# buck.net
KiCad netlist of a schematic drawn in Altium Designer
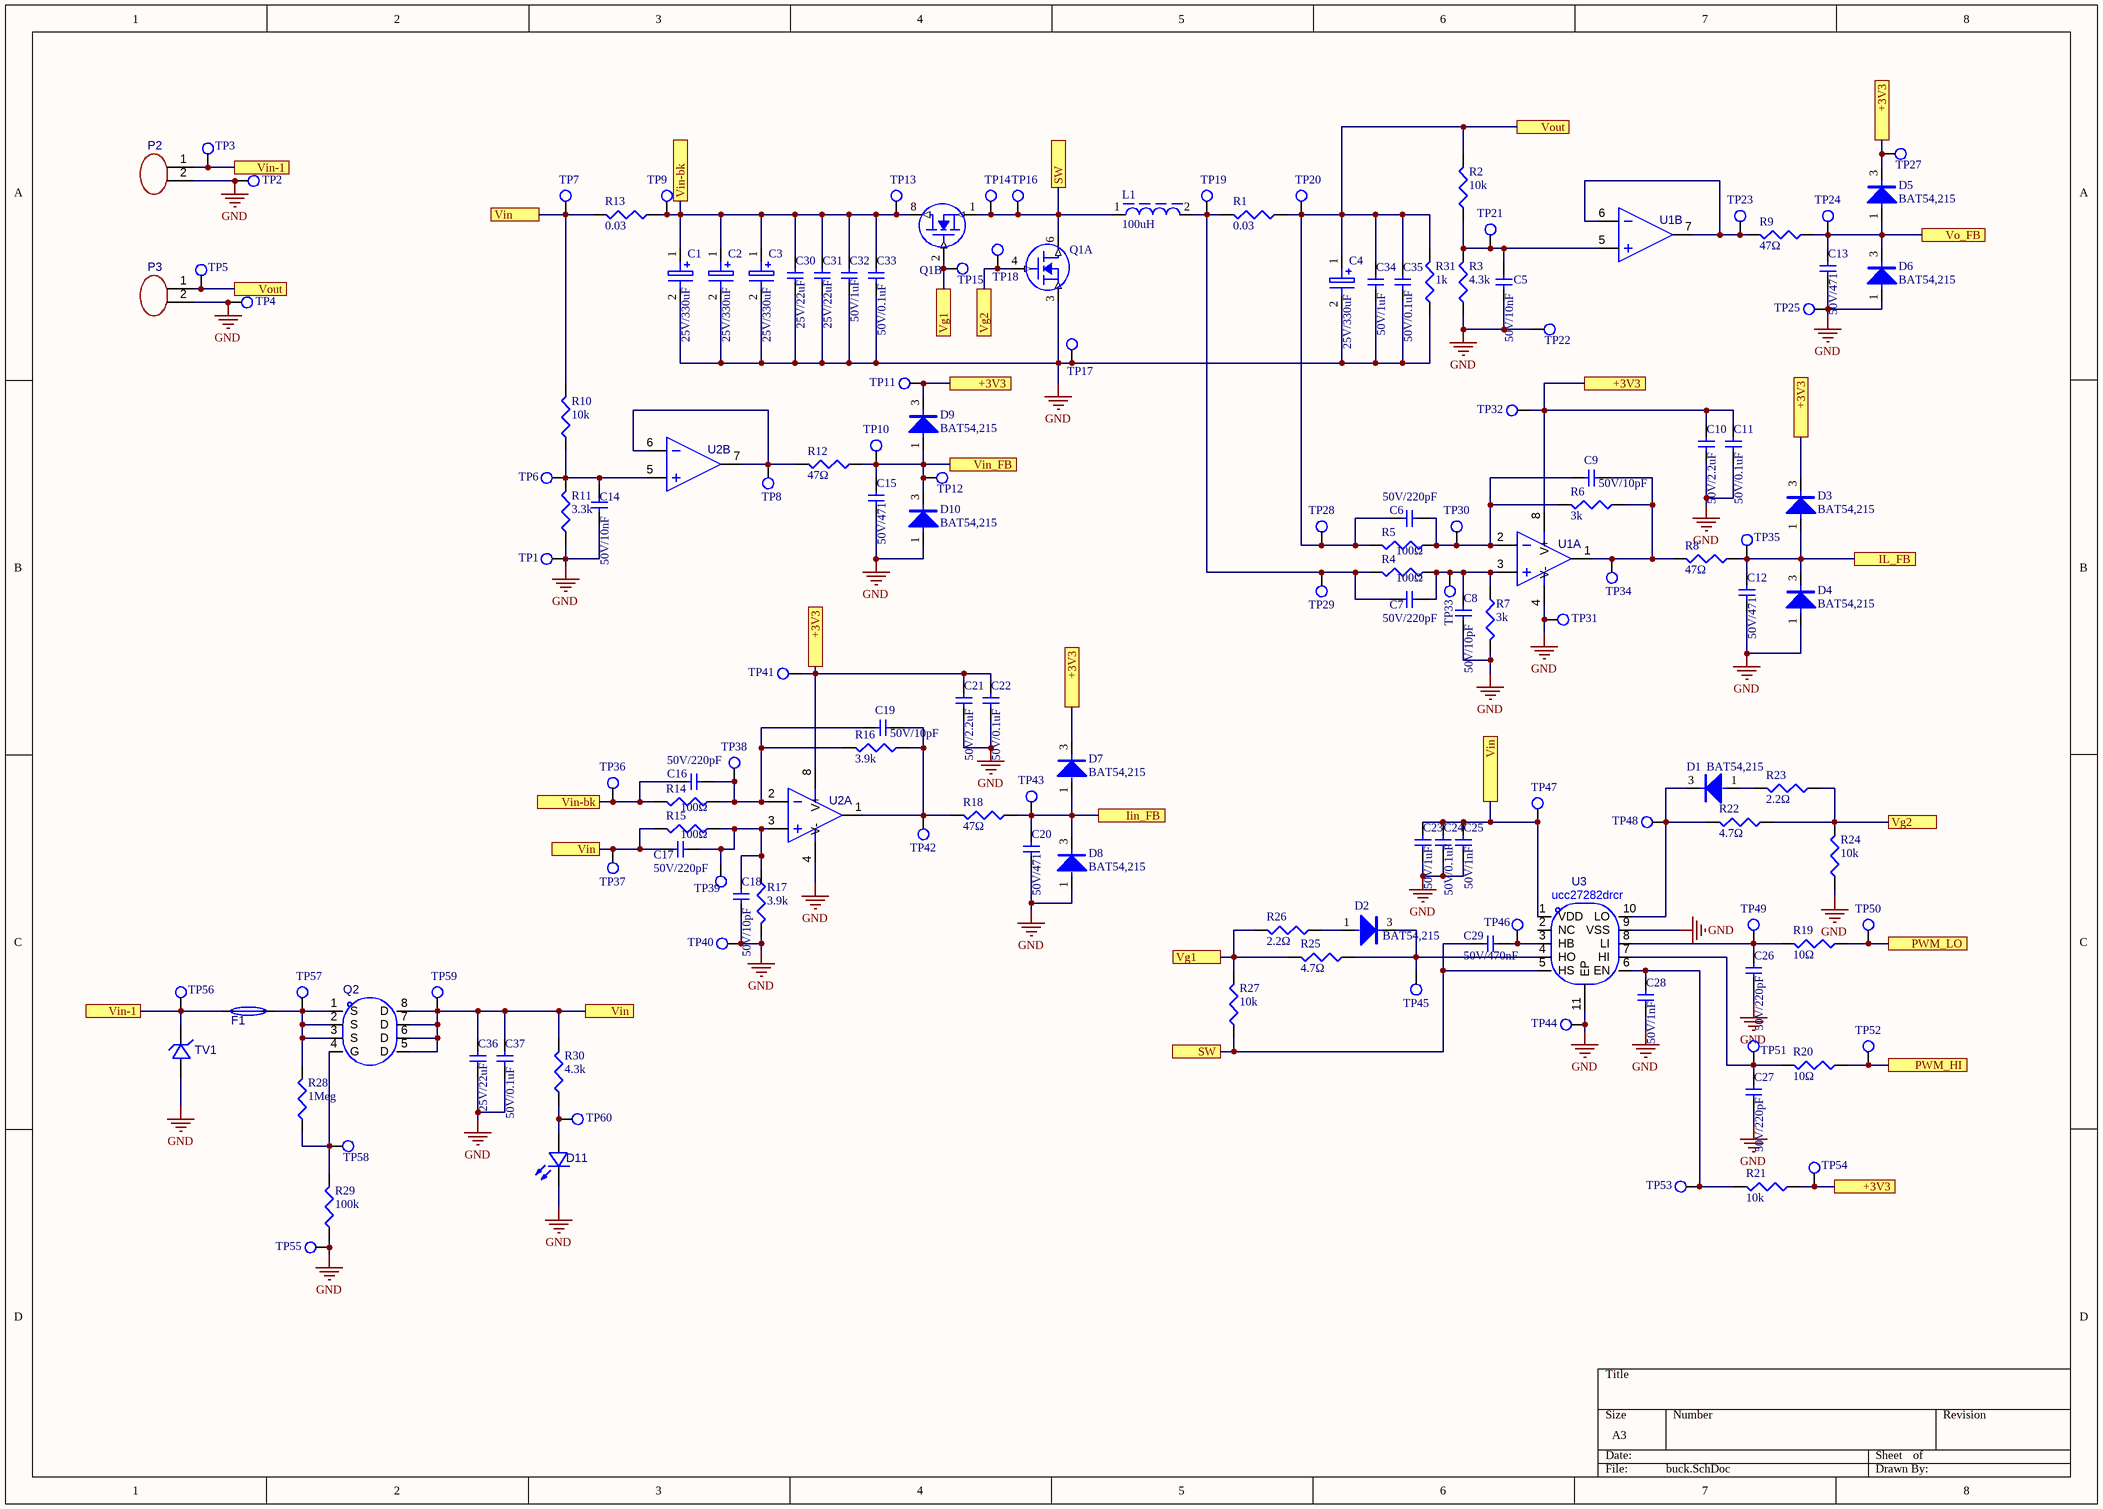
[diagram p0: buck.SchDoc]

(export (version "E")
  (design (tool "Eeschema 10.0.6"))
  (components
    (comp (ref "C1")
      (value "25V/330uF")
      (footprint "CAP-TH_BD8.0-P3.50-D0.6-FD")
      (description "25V/330uF,ERS1EM331F12OT,艾华,插件,D8xL12mm,irms=850mA,esr=0.086,")
      (libsource (lib "60W-PD-V2") (part "电解电容25V/330uF"))
    )
    (comp (ref "C2")
      (value "25V/330uF")
      (footprint "CAP-TH_BD8.0-P3.50-D0.6-FD")
      (description "25V/330uF,ERS1EM331F12OT,艾华,插件,D8xL12mm,irms=850mA,esr=0.086,")
      (libsource (lib "60W-PD-V2") (part "电解电容25V/330uF"))
    )
    (comp (ref "C3")
      (value "25V/330uF")
      (footprint "CAP-TH_BD8.0-P3.50-D0.6-FD")
      (description "25V/330uF,ERS1EM331F12OT,艾华,插件,D8xL12mm,irms=850mA,esr=0.086,")
      (libsource (lib "60W-PD-V2") (part "电解电容25V/330uF"))
    )
    (comp (ref "C4")
      (value "25V/330uF")
      (footprint "CAP-TH_BD8.0-P3.50-D0.6-FD")
      (description "25V/330uF,ERS1EM331F12OT,艾华,插件,D8xL12mm,irms=850mA,esr=0.086,")
      (libsource (lib "60W-PD-V2") (part "电解电容25V/330uF"))
    )
    (comp (ref "C5")
      (value "50V/10nF")
      (footprint "C0603")
      (description "0603,50V/10nF")
      (libsource (lib "60W-PD-V2") (part "C0603-50V/10nF"))
    )
    (comp (ref "C6")
      (value "50V/220pF")
      (footprint "C0603")
      (description "0603,50V/220pF")
      (libsource (lib "60W-PD-V2") (part "C0603-50V/220pF"))
    )
    (comp (ref "C7")
      (value "50V/220pF")
      (footprint "C0603")
      (description "0603,50V/220pF")
      (libsource (lib "60W-PD-V2") (part "C0603-50V/220pF"))
    )
    (comp (ref "C8")
      (value "50V/10pF")
      (footprint "C0603")
      (description "0603,50V/10pF")
      (libsource (lib "60W-PD-V2") (part "C0603-50V/10pF"))
    )
    (comp (ref "C9")
      (value "50V/10pF")
      (footprint "C0603")
      (description "0603,50V/10pF")
      (libsource (lib "60W-PD-V2") (part "C0603-50V/10pF"))
    )
    (comp (ref "C10")
      (value "50V/2.2uF")
      (footprint "C0805")
      (description "0805,50V/2.2uF,")
      (libsource (lib "60W-PD-V2") (part "C0805-50V/2.2uF"))
    )
    (comp (ref "C11")
      (value "50V/0.1uF")
      (footprint "C0603")
      (description "0603,50V/104")
      (libsource (lib "60W-PD-V2") (part "C0603-50V/104"))
    )
    (comp (ref "C12")
      (value "50V/471")
      (footprint "C0603")
      (description "0603,50V/471,")
      (libsource (lib "60W-PD-V2") (part "C0603-50V/471"))
    )
    (comp (ref "C13")
      (value "50V/471")
      (footprint "C0603")
      (description "0603,50V/471,")
      (libsource (lib "60W-PD-V2") (part "C0603-50V/471"))
    )
    (comp (ref "C14")
      (value "50V/10nF")
      (footprint "C0603")
      (description "0603,50V/10nF")
      (libsource (lib "60W-PD-V2") (part "C0603-50V/10nF"))
    )
    (comp (ref "C15")
      (value "50V/471")
      (footprint "C0603")
      (description "0603,50V/471,")
      (libsource (lib "60W-PD-V2") (part "C0603-50V/471"))
    )
    (comp (ref "C16")
      (value "50V/220pF")
      (footprint "C0603")
      (description "0603,50V/220pF")
      (libsource (lib "60W-PD-V2") (part "C0603-50V/220pF"))
    )
    (comp (ref "C17")
      (value "50V/220pF")
      (footprint "C0603")
      (description "0603,50V/220pF")
      (libsource (lib "60W-PD-V2") (part "C0603-50V/220pF"))
    )
    (comp (ref "C18")
      (value "50V/10pF")
      (footprint "C0603")
      (description "0603,50V/10pF")
      (libsource (lib "60W-PD-V2") (part "C0603-50V/10pF"))
    )
    (comp (ref "C19")
      (value "50V/10pF")
      (footprint "C0603")
      (description "0603,50V/10pF")
      (libsource (lib "60W-PD-V2") (part "C0603-50V/10pF"))
    )
    (comp (ref "C20")
      (value "50V/471")
      (footprint "C0603")
      (description "0603,50V/471,")
      (libsource (lib "60W-PD-V2") (part "C0603-50V/471"))
    )
    (comp (ref "C21")
      (value "50V/2.2uF")
      (footprint "C0805")
      (description "0805,50V/2.2uF,")
      (libsource (lib "60W-PD-V2") (part "C0805-50V/2.2uF"))
    )
    (comp (ref "C22")
      (value "50V/0.1uF")
      (footprint "C0603")
      (description "0603,50V/104")
      (libsource (lib "60W-PD-V2") (part "C0603-50V/104"))
    )
    (comp (ref "C23")
      (value "50V/1uF")
      (footprint "C0603")
      (description "0603,50V/1uF")
      (libsource (lib "60W-PD-V2") (part "C0603-50V/1uF"))
    )
    (comp (ref "C24")
      (value "50V/0.1uF")
      (footprint "C0603")
      (description "0603,50V/104")
      (libsource (lib "60W-PD-V2") (part "C0603-50V/104"))
    )
    (comp (ref "C25")
      (value "50V/1nF")
      (footprint "C0603")
      (description "0603,50V/1nF")
      (libsource (lib "60W-PD-V2") (part "C0603-50V/1nF"))
    )
    (comp (ref "C26")
      (value "50V/220pF")
      (footprint "C0603")
      (description "0603,50V/220pF")
      (libsource (lib "60W-PD-V2") (part "C0603-50V/220pF"))
    )
    (comp (ref "C27")
      (value "50V/220pF")
      (footprint "C0603")
      (description "0603,50V/220pF")
      (libsource (lib "60W-PD-V2") (part "C0603-50V/220pF"))
    )
    (comp (ref "C28")
      (value "50V/1nF")
      (footprint "C0603")
      (description "0603,50V/1nF")
      (libsource (lib "60W-PD-V2") (part "C0603-50V/1nF"))
    )
    (comp (ref "C29")
      (value "50V/470nF")
      (footprint "C0603")
      (description "0603,50V/470nF")
      (libsource (lib "60W-PD-V2") (part "C0603-50V/470nF"))
    )
    (comp (ref "C30")
      (value "25V/22uF")
      (footprint "C0805")
      (description "0805,25V/22uF,")
      (libsource (lib "60W-PD-V2") (part "C0805-25V/22uF"))
    )
    (comp (ref "C31")
      (value "25V/22uF")
      (footprint "C0805")
      (description "0805,25V/22uF,")
      (libsource (lib "60W-PD-V2") (part "C0805-25V/22uF"))
    )
    (comp (ref "C32")
      (value "50V/1uF")
      (footprint "C0603")
      (description "0603,50V/1uF")
      (libsource (lib "60W-PD-V2") (part "C0603-50V/1uF"))
    )
    (comp (ref "C33")
      (value "50V/0.1uF")
      (footprint "C0603")
      (description "0603,50V/104")
      (libsource (lib "60W-PD-V2") (part "C0603-50V/104"))
    )
    (comp (ref "C34")
      (value "50V/1uF")
      (footprint "C0603")
      (description "0603,50V/1uF")
      (libsource (lib "60W-PD-V2") (part "C0603-50V/1uF"))
    )
    (comp (ref "C35")
      (value "50V/0.1uF")
      (footprint "C0603")
      (description "0603,50V/104")
      (libsource (lib "60W-PD-V2") (part "C0603-50V/104"))
    )
    (comp (ref "C36")
      (value "25V/22uF")
      (footprint "C0805")
      (description "0805,25V/22uF,")
      (libsource (lib "60W-PD-V2") (part "C0805-25V/22uF"))
    )
    (comp (ref "C37")
      (value "50V/0.1uF")
      (footprint "C0603")
      (description "0603,50V/104")
      (libsource (lib "60W-PD-V2") (part "C0603-50V/104"))
    )
    (comp (ref "D1")
      (value "BAT54,215")
      (footprint "SOT-23_L2.9-W1.3-P1.90-LS2.4-BR")
      (description "BAT54,215,安世,SOT-23,肖特基二极管")
      (libsource (lib "60W-PD-V2") (part "二极管-BAT54,215"))
    )
    (comp (ref "D2")
      (value "BAT54,215")
      (footprint "SOT-23_L2.9-W1.3-P1.90-LS2.4-BR")
      (description "BAT54,215,安世,SOT-23,肖特基二极管")
      (libsource (lib "60W-PD-V2") (part "二极管-BAT54,215"))
    )
    (comp (ref "D3")
      (value "BAT54,215")
      (footprint "SOT-23_L2.9-W1.3-P1.90-LS2.4-BR")
      (description "BAT54,215,安世,SOT-23,肖特基二极管")
      (libsource (lib "60W-PD-V2") (part "二极管-BAT54,215"))
    )
    (comp (ref "D4")
      (value "BAT54,215")
      (footprint "SOT-23_L2.9-W1.3-P1.90-LS2.4-BR")
      (description "BAT54,215,安世,SOT-23,肖特基二极管")
      (libsource (lib "60W-PD-V2") (part "二极管-BAT54,215"))
    )
    (comp (ref "D5")
      (value "BAT54,215")
      (footprint "SOT-23_L2.9-W1.3-P1.90-LS2.4-BR")
      (description "BAT54,215,安世,SOT-23,肖特基二极管")
      (libsource (lib "60W-PD-V2") (part "二极管-BAT54,215"))
    )
    (comp (ref "D6")
      (value "BAT54,215")
      (footprint "SOT-23_L2.9-W1.3-P1.90-LS2.4-BR")
      (description "BAT54,215,安世,SOT-23,肖特基二极管")
      (libsource (lib "60W-PD-V2") (part "二极管-BAT54,215"))
    )
    (comp (ref "D7")
      (value "BAT54,215")
      (footprint "SOT-23_L2.9-W1.3-P1.90-LS2.4-BR")
      (description "BAT54,215,安世,SOT-23,肖特基二极管")
      (libsource (lib "60W-PD-V2") (part "二极管-BAT54,215"))
    )
    (comp (ref "D8")
      (value "BAT54,215")
      (footprint "SOT-23_L2.9-W1.3-P1.90-LS2.4-BR")
      (description "BAT54,215,安世,SOT-23,肖特基二极管")
      (libsource (lib "60W-PD-V2") (part "二极管-BAT54,215"))
    )
    (comp (ref "D9")
      (value "BAT54,215")
      (footprint "SOT-23_L2.9-W1.3-P1.90-LS2.4-BR")
      (description "BAT54,215,安世,SOT-23,肖特基二极管")
      (libsource (lib "60W-PD-V2") (part "二极管-BAT54,215"))
    )
    (comp (ref "D10")
      (value "BAT54,215")
      (footprint "SOT-23_L2.9-W1.3-P1.90-LS2.4-BR")
      (description "BAT54,215,安世,SOT-23,肖特基二极管")
      (libsource (lib "60W-PD-V2") (part "二极管-BAT54,215"))
    )
    (comp (ref "D11")
      (value "ncd0805c1")
      (footprint "LED0805-RD")
      (fields (field (name "MANUFACTURER") "国星光电") (field (name "MANUFACTURERPART") "NCD0805C1"))
      (libsource (lib "60W-PD-V2") (part "ncd0805c1"))
    )
    (comp (ref "F1")
      (value "bsmd1206c-1400t")
      (footprint "F1206")
      (description "类型:贴片式保险丝;额定电流:4A;额定电压 (AC):72V;额定电压:72V;分断能力:50A;")
      (fields (field (name "MANUFACTURER") "BHFUSE(佰宏)") (field (name "MANUFACTURERPART") "BSMD1206C-1400T"))
      (libsource (lib "60W-PD-V2") (part "bsmd1206c-1400t"))
    )
    (comp (ref "L1")
      (value "100uH")
      (footprint "IND-SMD_L13.5-W12.6")
      (description "100uH/5.5A,SMD,XR1365-101M,SMD,13.5x12.6mm,XR(祥如),i=5.5A,isat=7.5A")
      (libsource (lib "60W-PD-V2") (part "电感-100uH/5A"))
    )
    (comp (ref "P2")
      (value "wj500v-5.08-2p")
      (footprint "CONN-TH_2P-P5.00_WJ500V-5.08-2P")
      (fields
        (field (name "MANUFACTURER") "KANGNEX(康奈克斯电气)")
        (field (name "MANUFACTURERPART") "WJ500V-5.08-2P")
      )
      (libsource (lib "60W-PD-V2") (part "wj500v-5.08-2p"))
    )
    (comp (ref "P3")
      (value "wj500v-5.08-2p")
      (footprint "CONN-TH_2P-P5.00_WJ500V-5.08-2P")
      (fields
        (field (name "MANUFACTURER") "KANGNEX(康奈克斯电气)")
        (field (name "MANUFACTURERPART") "WJ500V-5.08-2P")
      )
      (libsource (lib "60W-PD-V2") (part "wj500v-5.08-2p"))
    )
    (comp (ref "Q1")
      (value "NCE6005AS")
      (footprint "SOP-8_L4.9-W3.9-P1.27-LS6.0-BL-2mos")
      (description "NCE6005AS,60V/5A,Rdson=35m,新洁能,2个N沟道")
      (libsource (lib "60W-PD-V2") (part "MOS管-60V/5A"))
    )
    (comp (ref "Q2")
      (value "ao4407a_c2841482")
      (footprint "SOP-8_L5.0-W4.0-P1.27-LS6.0-BL")
      (fields (field (name "MANUFACTURER") "UMW(友台半导体)") (field (name "MANUFACTURERPART") "AO4407A"))
      (libsource (lib "60W-PD-V2") (part "ao4407a_c2841482"))
    )
    (comp (ref "R1")
      (value "0.03")
      (footprint "R0805")
      (description "0805,0.03,RE0805FAR030,捷而瑞")
      (libsource (lib "60W-PD-V2") (part "R0805-0R03"))
    )
    (comp (ref "R2")
      (value "10k")
      (footprint "R0603")
      (description "0603,10k")
      (libsource (lib "60W-PD-V2") (part "R0603-10k"))
    )
    (comp (ref "R3")
      (value "4.3k")
      (footprint "R0603")
      (description "0603,4.3k")
      (libsource (lib "60W-PD-V2") (part "R0603-4.3k"))
    )
    (comp (ref "R4")
      (value "100Ω")
      (footprint "R0603")
      (description "0603,100Ω")
      (libsource (lib "60W-PD-V2") (part "R0603-100Ω"))
    )
    (comp (ref "R5")
      (value "100Ω")
      (footprint "R0603")
      (description "0603,100Ω")
      (libsource (lib "60W-PD-V2") (part "R0603-100Ω"))
    )
    (comp (ref "R6")
      (value "3k")
      (footprint "R0603")
      (description "0603,3k")
      (libsource (lib "60W-PD-V2") (part "R0603-3k"))
    )
    (comp (ref "R7")
      (value "3k")
      (footprint "R0603")
      (description "0603,3k")
      (libsource (lib "60W-PD-V2") (part "R0603-3k"))
    )
    (comp (ref "R8")
      (value "47Ω")
      (footprint "R0603")
      (description "0603,47Ω")
      (libsource (lib "60W-PD-V2") (part "R0603-47Ω"))
    )
    (comp (ref "R9")
      (value "47Ω")
      (footprint "R0603")
      (description "0603,47Ω")
      (libsource (lib "60W-PD-V2") (part "R0603-47Ω"))
    )
    (comp (ref "R10")
      (value "10k")
      (footprint "R0603")
      (description "0603,10k")
      (libsource (lib "60W-PD-V2") (part "R0603-10k"))
    )
    (comp (ref "R11")
      (value "3.3k")
      (footprint "R0603")
      (description "0603,3.3k")
      (libsource (lib "60W-PD-V2") (part "R0603-3.3k"))
    )
    (comp (ref "R12")
      (value "47Ω")
      (footprint "R0603")
      (description "0603,47Ω")
      (libsource (lib "60W-PD-V2") (part "R0603-47Ω"))
    )
    (comp (ref "R13")
      (value "0.03")
      (footprint "R0805")
      (description "0805,0.03,RE0805FAR030,捷而瑞")
      (libsource (lib "60W-PD-V2") (part "R0805-0R03"))
    )
    (comp (ref "R14")
      (value "100Ω")
      (footprint "R0603")
      (description "0603,100Ω")
      (libsource (lib "60W-PD-V2") (part "R0603-100Ω"))
    )
    (comp (ref "R15")
      (value "100Ω")
      (footprint "R0603")
      (description "0603,100Ω")
      (libsource (lib "60W-PD-V2") (part "R0603-100Ω"))
    )
    (comp (ref "R16")
      (value "3.9k")
      (footprint "R0603")
      (description "0603,3.9k")
      (libsource (lib "60W-PD-V2") (part "R0603-3.9k"))
    )
    (comp (ref "R17")
      (value "3.9k")
      (footprint "R0603")
      (description "0603,3.9k")
      (libsource (lib "60W-PD-V2") (part "R0603-3.9k"))
    )
    (comp (ref "R18")
      (value "47Ω")
      (footprint "R0603")
      (description "0603,47Ω")
      (libsource (lib "60W-PD-V2") (part "R0603-47Ω"))
    )
    (comp (ref "R19")
      (value "10Ω")
      (footprint "R0603")
      (description "0603,10Ω")
      (libsource (lib "60W-PD-V2") (part "R0603-10Ω"))
    )
    (comp (ref "R20")
      (value "10Ω")
      (footprint "R0603")
      (description "0603,10Ω")
      (libsource (lib "60W-PD-V2") (part "R0603-10Ω"))
    )
    (comp (ref "R21")
      (value "10k")
      (footprint "R0603")
      (description "0603,10k")
      (libsource (lib "60W-PD-V2") (part "R0603-10k"))
    )
    (comp (ref "R22")
      (value "4.7Ω")
      (footprint "R0603")
      (description "0603,4.7Ω")
      (libsource (lib "60W-PD-V2") (part "R0603-4.7Ω"))
    )
    (comp (ref "R23")
      (value "2.2Ω")
      (footprint "R0603")
      (description "0603,2.2Ω")
      (libsource (lib "60W-PD-V2") (part "R0603-2.2Ω"))
    )
    (comp (ref "R24")
      (value "10k")
      (footprint "R0603")
      (description "0603,10k")
      (libsource (lib "60W-PD-V2") (part "R0603-10k"))
    )
    (comp (ref "R25")
      (value "4.7Ω")
      (footprint "R0603")
      (description "0603,4.7Ω")
      (libsource (lib "60W-PD-V2") (part "R0603-4.7Ω"))
    )
    (comp (ref "R26")
      (value "2.2Ω")
      (footprint "R0603")
      (description "0603,2.2Ω")
      (libsource (lib "60W-PD-V2") (part "R0603-2.2Ω"))
    )
    (comp (ref "R27")
      (value "10k")
      (footprint "R0603")
      (description "0603,10k")
      (libsource (lib "60W-PD-V2") (part "R0603-10k"))
    )
    (comp (ref "R28")
      (value "1Meg")
      (footprint "R0603")
      (description "0603,1Meg")
      (libsource (lib "60W-PD-V2") (part "R0603-1Meg"))
    )
    (comp (ref "R29")
      (value "100k")
      (footprint "R0603")
      (description "0603,100k")
      (libsource (lib "60W-PD-V2") (part "R0603-100k"))
    )
    (comp (ref "R30")
      (value "4.3k")
      (footprint "R0603")
      (description "0603,4.3k")
      (libsource (lib "60W-PD-V2") (part "R0603-4.3k"))
    )
    (comp (ref "R31")
      (value "1k")
      (footprint "R1206")
      (description "1206,1k")
      (libsource (lib "60W-PD-V2") (part "R1206-1k"))
    )
    (comp (ref "TP1")
      (value "TP-pad0.8")
      (footprint "PAD0.8/1.6")
      (libsource (lib "60W-PD-V2") (part "TP-pad0.8"))
    )
    (comp (ref "TP2")
      (value "TP-pad0.8")
      (footprint "PAD0.8/1.6")
      (libsource (lib "60W-PD-V2") (part "TP-pad0.8"))
    )
    (comp (ref "TP3")
      (value "TP-pad0.8")
      (footprint "PAD0.8/1.6")
      (libsource (lib "60W-PD-V2") (part "TP-pad0.8"))
    )
    (comp (ref "TP4")
      (value "TP-pad0.8")
      (footprint "PAD0.8/1.6")
      (libsource (lib "60W-PD-V2") (part "TP-pad0.8"))
    )
    (comp (ref "TP5")
      (value "TP-pad0.8")
      (footprint "PAD0.8/1.6")
      (libsource (lib "60W-PD-V2") (part "TP-pad0.8"))
    )
    (comp (ref "TP6")
      (value "TEST POINT")
      (footprint "TP-1.5")
      (libsource (lib "60W-PD") (part "TEST POINT"))
    )
    (comp (ref "TP7")
      (value "TP-pad0.8")
      (footprint "PAD0.8/1.6")
      (libsource (lib "60W-PD-V2") (part "TP-pad0.8"))
    )
    (comp (ref "TP8")
      (value "TEST POINT")
      (footprint "TP-1.5")
      (libsource (lib "60W-PD") (part "TEST POINT"))
    )
    (comp (ref "TP9")
      (value "TEST POINT")
      (footprint "TP-1.5")
      (libsource (lib "60W-PD") (part "TEST POINT"))
    )
    (comp (ref "TP10")
      (value "TEST POINT")
      (footprint "TP-1.5")
      (libsource (lib "60W-PD") (part "TEST POINT"))
    )
    (comp (ref "TP11")
      (value "TEST POINT")
      (footprint "TP-1.5")
      (libsource (lib "60W-PD") (part "TEST POINT"))
    )
    (comp (ref "TP12")
      (value "TEST POINT")
      (footprint "TP-1.5")
      (libsource (lib "60W-PD") (part "TEST POINT"))
    )
    (comp (ref "TP13")
      (value "TP-pad0.8")
      (footprint "PAD0.8/1.6")
      (libsource (lib "60W-PD-V2") (part "TP-pad0.8"))
    )
    (comp (ref "TP14")
      (value "TP-pad0.8")
      (footprint "PAD0.8/1.6")
      (libsource (lib "60W-PD-V2") (part "TP-pad0.8"))
    )
    (comp (ref "TP15")
      (value "TP-pad0.8")
      (footprint "PAD0.8/1.6")
      (libsource (lib "60W-PD-V2") (part "TP-pad0.8"))
    )
    (comp (ref "TP16")
      (value "TP-pad0.8")
      (footprint "PAD0.8/1.6")
      (libsource (lib "60W-PD-V2") (part "TP-pad0.8"))
    )
    (comp (ref "TP17")
      (value "TP-pad0.8")
      (footprint "PAD0.8/1.6")
      (libsource (lib "60W-PD-V2") (part "TP-pad0.8"))
    )
    (comp (ref "TP18")
      (value "TP-pad0.8")
      (footprint "PAD0.8/1.6")
      (libsource (lib "60W-PD-V2") (part "TP-pad0.8"))
    )
    (comp (ref "TP19")
      (value "TP-pad0.8")
      (footprint "PAD0.8/1.6")
      (libsource (lib "60W-PD-V2") (part "TP-pad0.8"))
    )
    (comp (ref "TP20")
      (value "TP-pad0.8")
      (footprint "PAD0.8/1.6")
      (libsource (lib "60W-PD-V2") (part "TP-pad0.8"))
    )
    (comp (ref "TP21")
      (value "TEST POINT")
      (footprint "TP-1.5")
      (libsource (lib "60W-PD") (part "TEST POINT"))
    )
    (comp (ref "TP22")
      (value "TP-pad0.8")
      (footprint "PAD0.8/1.6")
      (libsource (lib "60W-PD-V2") (part "TP-pad0.8"))
    )
    (comp (ref "TP23")
      (value "TEST POINT")
      (footprint "TP-1.5")
      (libsource (lib "60W-PD") (part "TEST POINT"))
    )
    (comp (ref "TP24")
      (value "TEST POINT")
      (footprint "TP-1.5")
      (libsource (lib "60W-PD") (part "TEST POINT"))
    )
    (comp (ref "TP25")
      (value "TP-pad0.8")
      (footprint "PAD0.8/1.6")
      (libsource (lib "60W-PD-V2") (part "TP-pad0.8"))
    )
    (comp (ref "TP27")
      (value "TP-pad0.8")
      (footprint "PAD0.8/1.6")
      (libsource (lib "60W-PD-V2") (part "TP-pad0.8"))
    )
    (comp (ref "TP28")
      (value "TEST POINT")
      (footprint "TP-1.5")
      (libsource (lib "60W-PD") (part "TEST POINT"))
    )
    (comp (ref "TP29")
      (value "TEST POINT")
      (footprint "TP-1.5")
      (libsource (lib "60W-PD") (part "TEST POINT"))
    )
    (comp (ref "TP30")
      (value "TEST POINT")
      (footprint "TP-1.5")
      (libsource (lib "60W-PD") (part "TEST POINT"))
    )
    (comp (ref "TP31")
      (value "TP-pad0.8")
      (footprint "PAD0.8/1.6")
      (libsource (lib "60W-PD-V2") (part "TP-pad0.8"))
    )
    (comp (ref "TP32")
      (value "TP-pad0.8")
      (footprint "PAD0.8/1.6")
      (libsource (lib "60W-PD-V2") (part "TP-pad0.8"))
    )
    (comp (ref "TP33")
      (value "TEST POINT")
      (footprint "TP-1.5")
      (libsource (lib "60W-PD") (part "TEST POINT"))
    )
    (comp (ref "TP34")
      (value "TEST POINT")
      (footprint "TP-1.5")
      (libsource (lib "60W-PD") (part "TEST POINT"))
    )
    (comp (ref "TP35")
      (value "TEST POINT")
      (footprint "TP-1.5")
      (libsource (lib "60W-PD") (part "TEST POINT"))
    )
    (comp (ref "TP36")
      (value "TEST POINT")
      (footprint "TP-1.5")
      (libsource (lib "60W-PD") (part "TEST POINT"))
    )
    (comp (ref "TP37")
      (value "TEST POINT")
      (footprint "TP-1.5")
      (libsource (lib "60W-PD") (part "TEST POINT"))
    )
    (comp (ref "TP38")
      (value "TEST POINT")
      (footprint "TP-1.5")
      (libsource (lib "60W-PD") (part "TEST POINT"))
    )
    (comp (ref "TP39")
      (value "TEST POINT")
      (footprint "TP-1.5")
      (libsource (lib "60W-PD") (part "TEST POINT"))
    )
    (comp (ref "TP40")
      (value "TP-pad0.8")
      (footprint "PAD0.8/1.6")
      (libsource (lib "60W-PD-V2") (part "TP-pad0.8"))
    )
    (comp (ref "TP41")
      (value "TP-pad0.8")
      (footprint "PAD0.8/1.6")
      (libsource (lib "60W-PD-V2") (part "TP-pad0.8"))
    )
    (comp (ref "TP42")
      (value "TEST POINT")
      (footprint "TP-1.5")
      (libsource (lib "60W-PD") (part "TEST POINT"))
    )
    (comp (ref "TP43")
      (value "TEST POINT")
      (footprint "TP-1.5")
      (libsource (lib "60W-PD") (part "TEST POINT"))
    )
    (comp (ref "TP44")
      (value "TP-pad0.8")
      (footprint "PAD0.8/1.6")
      (libsource (lib "60W-PD-V2") (part "TP-pad0.8"))
    )
    (comp (ref "TP45")
      (value "TP-pad0.8")
      (footprint "PAD0.8/1.6")
      (libsource (lib "60W-PD-V2") (part "TP-pad0.8"))
    )
    (comp (ref "TP46")
      (value "TP-pad0.8")
      (footprint "PAD0.8/1.6")
      (libsource (lib "60W-PD-V2") (part "TP-pad0.8"))
    )
    (comp (ref "TP47")
      (value "TP-pad0.8")
      (footprint "PAD0.8/1.6")
      (libsource (lib "60W-PD-V2") (part "TP-pad0.8"))
    )
    (comp (ref "TP48")
      (value "TP-pad0.8")
      (footprint "PAD0.8/1.6")
      (libsource (lib "60W-PD-V2") (part "TP-pad0.8"))
    )
    (comp (ref "TP49")
      (value "TP-pad0.8")
      (footprint "PAD0.8/1.6")
      (libsource (lib "60W-PD-V2") (part "TP-pad0.8"))
    )
    (comp (ref "TP50")
      (value "TP-pad0.8")
      (footprint "PAD0.8/1.6")
      (libsource (lib "60W-PD-V2") (part "TP-pad0.8"))
    )
    (comp (ref "TP51")
      (value "TP-pad0.8")
      (footprint "PAD0.8/1.6")
      (libsource (lib "60W-PD-V2") (part "TP-pad0.8"))
    )
    (comp (ref "TP52")
      (value "TP-pad0.8")
      (footprint "PAD0.8/1.6")
      (libsource (lib "60W-PD-V2") (part "TP-pad0.8"))
    )
    (comp (ref "TP53")
      (value "TP-pad0.8")
      (footprint "PAD0.8/1.6")
      (libsource (lib "60W-PD-V2") (part "TP-pad0.8"))
    )
    (comp (ref "TP54")
      (value "TP-pad0.8")
      (footprint "PAD0.8/1.6")
      (libsource (lib "60W-PD-V2") (part "TP-pad0.8"))
    )
    (comp (ref "TP55")
      (value "TP-pad0.8")
      (footprint "PAD0.8/1.6")
      (libsource (lib "60W-PD-V2") (part "TP-pad0.8"))
    )
    (comp (ref "TP56")
      (value "TP-pad0.8")
      (footprint "PAD0.8/1.6")
      (libsource (lib "60W-PD-V2") (part "TP-pad0.8"))
    )
    (comp (ref "TP57")
      (value "TP-pad0.8")
      (footprint "PAD0.8/1.6")
      (libsource (lib "60W-PD-V2") (part "TP-pad0.8"))
    )
    (comp (ref "TP58")
      (value "TEST POINT")
      (footprint "TP-1.5")
      (libsource (lib "60W-PD") (part "TEST POINT"))
    )
    (comp (ref "TP59")
      (value "TP-pad0.8")
      (footprint "PAD0.8/1.6")
      (libsource (lib "60W-PD-V2") (part "TP-pad0.8"))
    )
    (comp (ref "TP60")
      (value "TEST POINT")
      (footprint "TP-1.5")
      (libsource (lib "60W-PD") (part "TEST POINT"))
    )
    (comp (ref "TV1")
      (value "smbj15a_c83846")
      (footprint "SMB_L4.6-W3.6-LS5.3-RD")
      (description "极性:单向;反向截止电压(Vrwm):15V;钳位电压:24.4V;峰值脉冲电流(Ipp):24.6A;峰值脉冲功率(Ppp):600W;击穿电压(VBR):16.7V;")
      (fields (field (name "MANUFACTURER") "Littelfuse(美国力特)") (field (name "MANUFACTURERPART") "SMBJ15A"))
      (libsource (lib "60W-PD-V2") (part "smbj15a_c83846"))
    )
    (comp (ref "U1")
      (value "tlv9062idgkr")
      (footprint "VSSOP-8_L3.0-W3.0-P0.65-LS4.9-BL")
      (description "放大器数:2;轨到轨:轨到轨输入,轨到轨输出;增益带宽积(GBW):10MHz;输入失调电压(Vos):1.6mV;压摆率(SR):55V/us;输入偏置电流(Ib):0.5pA;")
      (fields (field (name "MANUFACTURER") "TI(德州仪器)") (field (name "MANUFACTURERPART") "TLV9062IDGKR"))
      (libsource (lib "60W-PD") (part "tlv9062idgkr"))
    )
    (comp (ref "U2")
      (value "tlv9062idgkr")
      (footprint "VSSOP-8_L3.0-W3.0-P0.65-LS4.9-BL")
      (description "放大器数:2;轨到轨:轨到轨输入,轨到轨输出;增益带宽积(GBW):10MHz;输入失调电压(Vos):1.6mV;压摆率(SR):55V/us;输入偏置电流(Ib):0.5pA;")
      (fields (field (name "MANUFACTURER") "TI(德州仪器)") (field (name "MANUFACTURERPART") "TLV9062IDGKR"))
      (libsource (lib "60W-PD") (part "tlv9062idgkr"))
    )
    (comp (ref "U3")
      (value "ucc27282drcr")
      (footprint "VSON-10_L3.0-W3.0-P0.50-TL-EP")
      (description "驱动配置:半桥;负载类型:MOSFET;驱动通道数:2;灌电流(IOL):3A;拉电流(IOH):3A;工作电压:5.5V~16V;上升时间(tr):12ns;下降时间(tf):10ns;")
      (fields (field (name "MANUFACTURER") "TI(德州仪器)") (field (name "MANUFACTURERPART") "UCC27282DRCR"))
      (libsource (lib "60W-PD") (part "ucc27282drcr"))
    )
  )
  (nets
    (net (code "1") (name "/+3V3") (class "Default")
      (node (ref "C10") (pin "1") (pinfunction "1_1") (pintype "passive"))
      (node (ref "C11") (pin "1") (pinfunction "1_1") (pintype "passive"))
      (node (ref "C21") (pin "1") (pinfunction "1_1") (pintype "passive"))
      (node (ref "C22") (pin "1") (pinfunction "1_1") (pintype "passive"))
      (node (ref "D3") (pin "3") (pinfunction "K_3") (pintype "passive"))
      (node (ref "D5") (pin "3") (pinfunction "K_3") (pintype "passive"))
      (node (ref "D7") (pin "3") (pinfunction "K_3") (pintype "passive"))
      (node (ref "D9") (pin "3") (pinfunction "K_3") (pintype "passive"))
      (node (ref "R21") (pin "1") (pinfunction "1_1") (pintype "passive"))
      (node (ref "TP11") (pin "1") (pinfunction "1_1") (pintype "passive"))
      (node (ref "TP27") (pin "1") (pinfunction "1_1") (pintype "passive"))
      (node (ref "TP32") (pin "1") (pinfunction "1_1") (pintype "passive"))
      (node (ref "TP41") (pin "1") (pinfunction "1_1") (pintype "passive"))
      (node (ref "TP54") (pin "1") (pinfunction "1_1") (pintype "passive"))
      (node (ref "U1") (pin "8") (pinfunction "V+_8") (pintype "passive"))
      (node (ref "U2") (pin "8") (pinfunction "V+_8") (pintype "passive"))
    )
    (net (code "2") (name "/IL_FB") (class "Default")
      (node (ref "C12") (pin "1") (pinfunction "1_1") (pintype "passive"))
      (node (ref "D3") (pin "1") (pinfunction "A_1") (pintype "passive"))
      (node (ref "D4") (pin "3") (pinfunction "K_3") (pintype "passive"))
      (node (ref "R8") (pin "1") (pinfunction "1_1") (pintype "passive"))
      (node (ref "TP35") (pin "1") (pinfunction "1_1") (pintype "passive"))
    )
    (net (code "3") (name "/Iin_FB") (class "Default")
      (node (ref "C20") (pin "1") (pinfunction "1_1") (pintype "passive"))
      (node (ref "D7") (pin "1") (pinfunction "A_1") (pintype "passive"))
      (node (ref "D8") (pin "3") (pinfunction "K_3") (pintype "passive"))
      (node (ref "R18") (pin "1") (pinfunction "1_1") (pintype "passive"))
      (node (ref "TP43") (pin "1") (pinfunction "1_1") (pintype "passive"))
    )
    (net (code "4") (name "/PWM_HI") (class "Default")
      (node (ref "R20") (pin "1") (pinfunction "1_1") (pintype "passive"))
      (node (ref "TP52") (pin "1") (pinfunction "1_1") (pintype "passive"))
    )
    (net (code "5") (name "/PWM_LO") (class "Default")
      (node (ref "R19") (pin "1") (pinfunction "1_1") (pintype "passive"))
      (node (ref "TP50") (pin "1") (pinfunction "1_1") (pintype "passive"))
    )
    (net (code "6") (name "/SW") (class "Default")
      (node (ref "C29") (pin "1") (pinfunction "1_1") (pintype "passive"))
      (node (ref "L1") (pin "1") (pinfunction "1_1") (pintype "passive"))
      (node (ref "Q1") (pin "1") (pinfunction "S_1") (pintype "input"))
      (node (ref "Q1") (pin "6") (pinfunction "D_6") (pintype "output"))
      (node (ref "R27") (pin "1") (pinfunction "1_1") (pintype "passive"))
      (node (ref "TP14") (pin "1") (pinfunction "1_1") (pintype "passive"))
      (node (ref "TP16") (pin "1") (pinfunction "1_1") (pintype "passive"))
      (node (ref "U3") (pin "5") (pinfunction "HS_5") (pintype "passive"))
    )
    (net (code "7") (name "/Vg1") (class "Default")
      (node (ref "Q1") (pin "2") (pinfunction "G_2") (pintype "input"))
      (node (ref "R25") (pin "2") (pinfunction "2_2") (pintype "passive"))
      (node (ref "R26") (pin "2") (pinfunction "2_2") (pintype "passive"))
      (node (ref "R27") (pin "2") (pinfunction "2_2") (pintype "passive"))
      (node (ref "TP15") (pin "1") (pinfunction "1_1") (pintype "passive"))
    )
    (net (code "8") (name "/Vg2") (class "Default")
      (node (ref "Q1") (pin "4") (pinfunction "G_4") (pintype "input"))
      (node (ref "R22") (pin "1") (pinfunction "1_1") (pintype "passive"))
      (node (ref "R23") (pin "1") (pinfunction "1_1") (pintype "passive"))
      (node (ref "R24") (pin "2") (pinfunction "2_2") (pintype "passive"))
      (node (ref "TP18") (pin "1") (pinfunction "1_1") (pintype "passive"))
    )
    (net (code "9") (name "/Vin") (class "Default")
      (node (ref "C17") (pin "1") (pinfunction "1_1") (pintype "passive"))
      (node (ref "C23") (pin "1") (pinfunction "1_1") (pintype "passive"))
      (node (ref "C24") (pin "1") (pinfunction "1_1") (pintype "passive"))
      (node (ref "C25") (pin "1") (pinfunction "1_1") (pintype "passive"))
      (node (ref "C36") (pin "1") (pinfunction "1_1") (pintype "passive"))
      (node (ref "C37") (pin "1") (pinfunction "1_1") (pintype "passive"))
      (node (ref "Q2") (pin "5") (pinfunction "D_5") (pintype "passive"))
      (node (ref "Q2") (pin "6") (pinfunction "D_6") (pintype "passive"))
      (node (ref "Q2") (pin "7") (pinfunction "D_7") (pintype "passive"))
      (node (ref "Q2") (pin "8") (pinfunction "D_8") (pintype "passive"))
      (node (ref "R10") (pin "2") (pinfunction "2_2") (pintype "passive"))
      (node (ref "R13") (pin "2") (pinfunction "2_2") (pintype "passive"))
      (node (ref "R15") (pin "2") (pinfunction "2_2") (pintype "passive"))
      (node (ref "R30") (pin "2") (pinfunction "2_2") (pintype "passive"))
      (node (ref "TP37") (pin "1") (pinfunction "1_1") (pintype "passive"))
      (node (ref "TP47") (pin "1") (pinfunction "1_1") (pintype "passive"))
      (node (ref "TP59") (pin "1") (pinfunction "1_1") (pintype "passive"))
      (node (ref "TP7") (pin "1") (pinfunction "1_1") (pintype "passive"))
      (node (ref "U3") (pin "1") (pinfunction "VDD_1") (pintype "passive"))
    )
    (net (code "10") (name "/Vin-1") (class "Default")
      (node (ref "F1") (pin "1") (pinfunction "1_1") (pintype "passive"))
      (node (ref "P2") (pin "1") (pinfunction "1_1") (pintype "passive"))
      (node (ref "TP3") (pin "1") (pinfunction "1_1") (pintype "passive"))
      (node (ref "TP56") (pin "1") (pinfunction "1_1") (pintype "passive"))
      (node (ref "TV1") (pin "1") (pinfunction "1_1") (pintype "passive"))
    )
    (net (code "11") (name "/Vin-bk") (class "Default")
      (node (ref "C1") (pin "1") (pinfunction "1_1") (pintype "passive"))
      (node (ref "C16") (pin "1") (pinfunction "1_1") (pintype "passive"))
      (node (ref "C2") (pin "1") (pinfunction "1_1") (pintype "passive"))
      (node (ref "C3") (pin "1") (pinfunction "1_1") (pintype "passive"))
      (node (ref "C30") (pin "1") (pinfunction "1_1") (pintype "passive"))
      (node (ref "C31") (pin "1") (pinfunction "1_1") (pintype "passive"))
      (node (ref "C32") (pin "1") (pinfunction "1_1") (pintype "passive"))
      (node (ref "C33") (pin "1") (pinfunction "1_1") (pintype "passive"))
      (node (ref "Q1") (pin "8") (pinfunction "D_8") (pintype "output"))
      (node (ref "R13") (pin "1") (pinfunction "1_1") (pintype "passive"))
      (node (ref "R14") (pin "2") (pinfunction "2_2") (pintype "passive"))
      (node (ref "TP13") (pin "1") (pinfunction "1_1") (pintype "passive"))
      (node (ref "TP36") (pin "1") (pinfunction "1_1") (pintype "passive"))
      (node (ref "TP9") (pin "1") (pinfunction "1_1") (pintype "passive"))
    )
    (net (code "12") (name "/Vin_FB") (class "Default")
      (node (ref "C15") (pin "1") (pinfunction "1_1") (pintype "passive"))
      (node (ref "D10") (pin "3") (pinfunction "K_3") (pintype "passive"))
      (node (ref "D9") (pin "1") (pinfunction "A_1") (pintype "passive"))
      (node (ref "R12") (pin "1") (pinfunction "1_1") (pintype "passive"))
      (node (ref "TP10") (pin "1") (pinfunction "1_1") (pintype "passive"))
      (node (ref "TP12") (pin "1") (pinfunction "1_1") (pintype "passive"))
    )
    (net (code "13") (name "/Vo_FB") (class "Default")
      (node (ref "C13") (pin "1") (pinfunction "1_1") (pintype "passive"))
      (node (ref "D5") (pin "1") (pinfunction "A_1") (pintype "passive"))
      (node (ref "D6") (pin "3") (pinfunction "K_3") (pintype "passive"))
      (node (ref "R9") (pin "1") (pinfunction "1_1") (pintype "passive"))
      (node (ref "TP24") (pin "1") (pinfunction "1_1") (pintype "passive"))
    )
    (net (code "14") (name "/Vout") (class "Default")
      (node (ref "C34") (pin "1") (pinfunction "1_1") (pintype "passive"))
      (node (ref "C35") (pin "1") (pinfunction "1_1") (pintype "passive"))
      (node (ref "C4") (pin "1") (pinfunction "1_1") (pintype "passive"))
      (node (ref "C6") (pin "1") (pinfunction "1_1") (pintype "passive"))
      (node (ref "P3") (pin "1") (pinfunction "1_1") (pintype "passive"))
      (node (ref "R1") (pin "1") (pinfunction "1_1") (pintype "passive"))
      (node (ref "R2") (pin "2") (pinfunction "2_2") (pintype "passive"))
      (node (ref "R31") (pin "2") (pinfunction "2_2") (pintype "passive"))
      (node (ref "R5") (pin "2") (pinfunction "2_2") (pintype "passive"))
      (node (ref "TP20") (pin "1") (pinfunction "1_1") (pintype "passive"))
      (node (ref "TP28") (pin "1") (pinfunction "1_1") (pintype "passive"))
      (node (ref "TP5") (pin "1") (pinfunction "1_1") (pintype "passive"))
    )
    (net (code "15") (name "GND") (class "Default")
      (node (ref "C1") (pin "2") (pinfunction "2_2") (pintype "passive"))
      (node (ref "C10") (pin "2") (pinfunction "2_2") (pintype "passive"))
      (node (ref "C11") (pin "2") (pinfunction "2_2") (pintype "passive"))
      (node (ref "C12") (pin "2") (pinfunction "2_2") (pintype "passive"))
      (node (ref "C13") (pin "2") (pinfunction "2_2") (pintype "passive"))
      (node (ref "C14") (pin "2") (pinfunction "2_2") (pintype "passive"))
      (node (ref "C15") (pin "2") (pinfunction "2_2") (pintype "passive"))
      (node (ref "C18") (pin "2") (pinfunction "2_2") (pintype "passive"))
      (node (ref "C2") (pin "2") (pinfunction "2_2") (pintype "passive"))
      (node (ref "C20") (pin "2") (pinfunction "2_2") (pintype "passive"))
      (node (ref "C21") (pin "2") (pinfunction "2_2") (pintype "passive"))
      (node (ref "C22") (pin "2") (pinfunction "2_2") (pintype "passive"))
      (node (ref "C23") (pin "2") (pinfunction "2_2") (pintype "passive"))
      (node (ref "C24") (pin "2") (pinfunction "2_2") (pintype "passive"))
      (node (ref "C25") (pin "2") (pinfunction "2_2") (pintype "passive"))
      (node (ref "C26") (pin "2") (pinfunction "2_2") (pintype "passive"))
      (node (ref "C27") (pin "2") (pinfunction "2_2") (pintype "passive"))
      (node (ref "C28") (pin "2") (pinfunction "2_2") (pintype "passive"))
      (node (ref "C3") (pin "2") (pinfunction "2_2") (pintype "passive"))
      (node (ref "C30") (pin "2") (pinfunction "2_2") (pintype "passive"))
      (node (ref "C31") (pin "2") (pinfunction "2_2") (pintype "passive"))
      (node (ref "C32") (pin "2") (pinfunction "2_2") (pintype "passive"))
      (node (ref "C33") (pin "2") (pinfunction "2_2") (pintype "passive"))
      (node (ref "C34") (pin "2") (pinfunction "2_2") (pintype "passive"))
      (node (ref "C35") (pin "2") (pinfunction "2_2") (pintype "passive"))
      (node (ref "C36") (pin "2") (pinfunction "2_2") (pintype "passive"))
      (node (ref "C37") (pin "2") (pinfunction "2_2") (pintype "passive"))
      (node (ref "C4") (pin "2") (pinfunction "2_2") (pintype "passive"))
      (node (ref "C5") (pin "2") (pinfunction "2_2") (pintype "passive"))
      (node (ref "C8") (pin "2") (pinfunction "2_2") (pintype "passive"))
      (node (ref "D10") (pin "1") (pinfunction "A_1") (pintype "passive"))
      (node (ref "D11") (pin "1") (pinfunction "K_1") (pintype "passive"))
      (node (ref "D4") (pin "1") (pinfunction "A_1") (pintype "passive"))
      (node (ref "D6") (pin "1") (pinfunction "A_1") (pintype "passive"))
      (node (ref "D8") (pin "1") (pinfunction "A_1") (pintype "passive"))
      (node (ref "P2") (pin "2") (pinfunction "2_2") (pintype "passive"))
      (node (ref "P3") (pin "2") (pinfunction "2_2") (pintype "passive"))
      (node (ref "Q1") (pin "3") (pinfunction "S_3") (pintype "input"))
      (node (ref "R11") (pin "1") (pinfunction "1_1") (pintype "passive"))
      (node (ref "R17") (pin "2") (pinfunction "2_2") (pintype "passive"))
      (node (ref "R24") (pin "1") (pinfunction "1_1") (pintype "passive"))
      (node (ref "R29") (pin "1") (pinfunction "1_1") (pintype "passive"))
      (node (ref "R3") (pin "1") (pinfunction "1_1") (pintype "passive"))
      (node (ref "R31") (pin "1") (pinfunction "1_1") (pintype "passive"))
      (node (ref "R7") (pin "2") (pinfunction "2_2") (pintype "passive"))
      (node (ref "TP1") (pin "1") (pinfunction "1_1") (pintype "passive"))
      (node (ref "TP17") (pin "1") (pinfunction "1_1") (pintype "passive"))
      (node (ref "TP2") (pin "1") (pinfunction "1_1") (pintype "passive"))
      (node (ref "TP22") (pin "1") (pinfunction "1_1") (pintype "passive"))
      (node (ref "TP25") (pin "1") (pinfunction "1_1") (pintype "passive"))
      (node (ref "TP31") (pin "1") (pinfunction "1_1") (pintype "passive"))
      (node (ref "TP4") (pin "1") (pinfunction "1_1") (pintype "passive"))
      (node (ref "TP40") (pin "1") (pinfunction "1_1") (pintype "passive"))
      (node (ref "TP44") (pin "1") (pinfunction "1_1") (pintype "passive"))
      (node (ref "TP55") (pin "1") (pinfunction "1_1") (pintype "passive"))
      (node (ref "TV1") (pin "2") (pinfunction "2_2") (pintype "passive"))
      (node (ref "U1") (pin "4") (pinfunction "V-_4") (pintype "passive"))
      (node (ref "U2") (pin "4") (pinfunction "V-_4") (pintype "passive"))
      (node (ref "U3") (pin "11") (pinfunction "EP_11") (pintype "passive"))
      (node (ref "U3") (pin "9") (pinfunction "VSS_9") (pintype "passive"))
    )
    (net (code "16") (name "Net-(C7-Pad1)") (class "Default")
      (node (ref "C7") (pin "1") (pinfunction "1_1") (pintype "passive"))
      (node (ref "L1") (pin "2") (pinfunction "2_2") (pintype "passive"))
      (node (ref "R1") (pin "2") (pinfunction "2_2") (pintype "passive"))
      (node (ref "R4") (pin "2") (pinfunction "2_2") (pintype "passive"))
      (node (ref "TP19") (pin "1") (pinfunction "1_1") (pintype "passive"))
      (node (ref "TP29") (pin "1") (pinfunction "1_1") (pintype "passive"))
    )
    (net (code "17") (name "Net-(D1-A)") (class "Default")
      (node (ref "D1") (pin "1") (pinfunction "A_1") (pintype "passive"))
      (node (ref "R23") (pin "2") (pinfunction "2_2") (pintype "passive"))
    )
    (net (code "18") (name "Net-(D1-K)") (class "Default")
      (node (ref "D1") (pin "3") (pinfunction "K_3") (pintype "passive"))
      (node (ref "R22") (pin "2") (pinfunction "2_2") (pintype "passive"))
      (node (ref "TP48") (pin "1") (pinfunction "1_1") (pintype "passive"))
      (node (ref "U3") (pin "10") (pinfunction "LO_10") (pintype "passive"))
    )
    (net (code "19") (name "Net-(D2-A)") (class "Default")
      (node (ref "D2") (pin "1") (pinfunction "A_1") (pintype "passive"))
      (node (ref "R26") (pin "1") (pinfunction "1_1") (pintype "passive"))
    )
    (net (code "20") (name "Net-(D2-K)") (class "Default")
      (node (ref "D2") (pin "3") (pinfunction "K_3") (pintype "passive"))
      (node (ref "R25") (pin "1") (pinfunction "1_1") (pintype "passive"))
      (node (ref "TP45") (pin "1") (pinfunction "1_1") (pintype "passive"))
      (node (ref "U3") (pin "4") (pinfunction "HO_4") (pintype "passive"))
    )
    (net (code "21") (name "Net-(D11-A)") (class "Default")
      (node (ref "D11") (pin "2") (pinfunction "A_2") (pintype "passive"))
      (node (ref "R30") (pin "1") (pinfunction "1_1") (pintype "passive"))
      (node (ref "TP60") (pin "1") (pinfunction "1_1") (pintype "passive"))
    )
    (net (code "22") (name "Net-(F1-Pad2)") (class "Default")
      (node (ref "F1") (pin "2") (pinfunction "2_2") (pintype "passive"))
      (node (ref "Q2") (pin "1") (pinfunction "S_1") (pintype "passive"))
      (node (ref "Q2") (pin "2") (pinfunction "S_2") (pintype "passive"))
      (node (ref "Q2") (pin "3") (pinfunction "S_3") (pintype "passive"))
      (node (ref "R28") (pin "2") (pinfunction "2_2") (pintype "passive"))
      (node (ref "TP57") (pin "1") (pinfunction "1_1") (pintype "passive"))
    )
    (net (code "23") (name "Net-(Q2-G)") (class "Default")
      (node (ref "Q2") (pin "4") (pinfunction "G_4") (pintype "passive"))
      (node (ref "R28") (pin "1") (pinfunction "1_1") (pintype "passive"))
      (node (ref "R29") (pin "2") (pinfunction "2_2") (pintype "passive"))
      (node (ref "TP58") (pin "1") (pinfunction "1_1") (pintype "passive"))
    )
    (net (code "24") (name "Net-(U1A-IN1+)") (class "Default")
      (node (ref "C7") (pin "2") (pinfunction "2_2") (pintype "passive"))
      (node (ref "C8") (pin "1") (pinfunction "1_1") (pintype "passive"))
      (node (ref "R4") (pin "1") (pinfunction "1_1") (pintype "passive"))
      (node (ref "R7") (pin "1") (pinfunction "1_1") (pintype "passive"))
      (node (ref "TP33") (pin "1") (pinfunction "1_1") (pintype "passive"))
      (node (ref "U1") (pin "3") (pinfunction "IN1+_3") (pintype "passive"))
    )
    (net (code "25") (name "Net-(U1A-IN1-)") (class "Default")
      (node (ref "C6") (pin "2") (pinfunction "2_2") (pintype "passive"))
      (node (ref "C9") (pin "1") (pinfunction "1_1") (pintype "passive"))
      (node (ref "R5") (pin "1") (pinfunction "1_1") (pintype "passive"))
      (node (ref "R6") (pin "2") (pinfunction "2_2") (pintype "passive"))
      (node (ref "TP30") (pin "1") (pinfunction "1_1") (pintype "passive"))
      (node (ref "U1") (pin "2") (pinfunction "IN1-_2") (pintype "passive"))
    )
    (net (code "26") (name "Net-(U1A-OUT1)") (class "Default")
      (node (ref "C9") (pin "2") (pinfunction "2_2") (pintype "passive"))
      (node (ref "R6") (pin "1") (pinfunction "1_1") (pintype "passive"))
      (node (ref "R8") (pin "2") (pinfunction "2_2") (pintype "passive"))
      (node (ref "TP34") (pin "1") (pinfunction "1_1") (pintype "passive"))
      (node (ref "U1") (pin "1") (pinfunction "OUT1_1") (pintype "passive"))
    )
    (net (code "27") (name "Net-(U1B-IN2+)") (class "Default")
      (node (ref "C5") (pin "1") (pinfunction "1_1") (pintype "passive"))
      (node (ref "R2") (pin "1") (pinfunction "1_1") (pintype "passive"))
      (node (ref "R3") (pin "2") (pinfunction "2_2") (pintype "passive"))
      (node (ref "TP21") (pin "1") (pinfunction "1_1") (pintype "passive"))
      (node (ref "U1") (pin "5") (pinfunction "IN2+_5") (pintype "passive"))
    )
    (net (code "28") (name "Net-(U1B-IN2-)") (class "Default")
      (node (ref "R9") (pin "2") (pinfunction "2_2") (pintype "passive"))
      (node (ref "TP23") (pin "1") (pinfunction "1_1") (pintype "passive"))
      (node (ref "U1") (pin "6") (pinfunction "IN2-_6") (pintype "passive"))
      (node (ref "U1") (pin "7") (pinfunction "OUT2_7") (pintype "passive"))
    )
    (net (code "29") (name "Net-(U2A-IN1+)") (class "Default")
      (node (ref "C17") (pin "2") (pinfunction "2_2") (pintype "passive"))
      (node (ref "C18") (pin "1") (pinfunction "1_1") (pintype "passive"))
      (node (ref "R15") (pin "1") (pinfunction "1_1") (pintype "passive"))
      (node (ref "R17") (pin "1") (pinfunction "1_1") (pintype "passive"))
      (node (ref "TP39") (pin "1") (pinfunction "1_1") (pintype "passive"))
      (node (ref "U2") (pin "3") (pinfunction "IN1+_3") (pintype "passive"))
    )
    (net (code "30") (name "Net-(U2A-IN1-)") (class "Default")
      (node (ref "C16") (pin "2") (pinfunction "2_2") (pintype "passive"))
      (node (ref "C19") (pin "1") (pinfunction "1_1") (pintype "passive"))
      (node (ref "R14") (pin "1") (pinfunction "1_1") (pintype "passive"))
      (node (ref "R16") (pin "2") (pinfunction "2_2") (pintype "passive"))
      (node (ref "TP38") (pin "1") (pinfunction "1_1") (pintype "passive"))
      (node (ref "U2") (pin "2") (pinfunction "IN1-_2") (pintype "passive"))
    )
    (net (code "31") (name "Net-(U2A-OUT1)") (class "Default")
      (node (ref "C19") (pin "2") (pinfunction "2_2") (pintype "passive"))
      (node (ref "R16") (pin "1") (pinfunction "1_1") (pintype "passive"))
      (node (ref "R18") (pin "2") (pinfunction "2_2") (pintype "passive"))
      (node (ref "TP42") (pin "1") (pinfunction "1_1") (pintype "passive"))
      (node (ref "U2") (pin "1") (pinfunction "OUT1_1") (pintype "passive"))
    )
    (net (code "32") (name "Net-(U2B-IN2+)") (class "Default")
      (node (ref "C14") (pin "1") (pinfunction "1_1") (pintype "passive"))
      (node (ref "R10") (pin "1") (pinfunction "1_1") (pintype "passive"))
      (node (ref "R11") (pin "2") (pinfunction "2_2") (pintype "passive"))
      (node (ref "TP6") (pin "1") (pinfunction "1_1") (pintype "passive"))
      (node (ref "U2") (pin "5") (pinfunction "IN2+_5") (pintype "passive"))
    )
    (net (code "33") (name "Net-(U2B-IN2-)") (class "Default")
      (node (ref "R12") (pin "2") (pinfunction "2_2") (pintype "passive"))
      (node (ref "TP8") (pin "1") (pinfunction "1_1") (pintype "passive"))
      (node (ref "U2") (pin "6") (pinfunction "IN2-_6") (pintype "passive"))
      (node (ref "U2") (pin "7") (pinfunction "OUT2_7") (pintype "passive"))
    )
    (net (code "34") (name "Net-(U3-EN)") (class "Default")
      (node (ref "C28") (pin "1") (pinfunction "1_1") (pintype "passive"))
      (node (ref "R21") (pin "2") (pinfunction "2_2") (pintype "passive"))
      (node (ref "TP53") (pin "1") (pinfunction "1_1") (pintype "passive"))
      (node (ref "U3") (pin "6") (pinfunction "EN_6") (pintype "passive"))
    )
    (net (code "35") (name "Net-(U3-HB)") (class "Default")
      (node (ref "C29") (pin "2") (pinfunction "2_2") (pintype "passive"))
      (node (ref "TP46") (pin "1") (pinfunction "1_1") (pintype "passive"))
      (node (ref "U3") (pin "3") (pinfunction "HB_3") (pintype "passive"))
    )
    (net (code "36") (name "Net-(U3-HI)") (class "Default")
      (node (ref "C27") (pin "1") (pinfunction "1_1") (pintype "passive"))
      (node (ref "R20") (pin "2") (pinfunction "2_2") (pintype "passive"))
      (node (ref "TP51") (pin "1") (pinfunction "1_1") (pintype "passive"))
      (node (ref "U3") (pin "7") (pinfunction "HI_7") (pintype "passive"))
    )
    (net (code "37") (name "Net-(U3-LI)") (class "Default")
      (node (ref "C26") (pin "1") (pinfunction "1_1") (pintype "passive"))
      (node (ref "R19") (pin "2") (pinfunction "2_2") (pintype "passive"))
      (node (ref "TP49") (pin "1") (pinfunction "1_1") (pintype "passive"))
      (node (ref "U3") (pin "8") (pinfunction "LI_8") (pintype "passive"))
    )
    (net (code "38") (name "unconnected-(U3-NC-Pad2)") (class "Default")
      (node (ref "U3") (pin "2") (pinfunction "NC_2") (pintype "passive"))
    )
  )
)
